# CAN_Humidity_Sensor_HB_LED_IR.net
KiCad netlist of a schematic drawn in Altium Designer
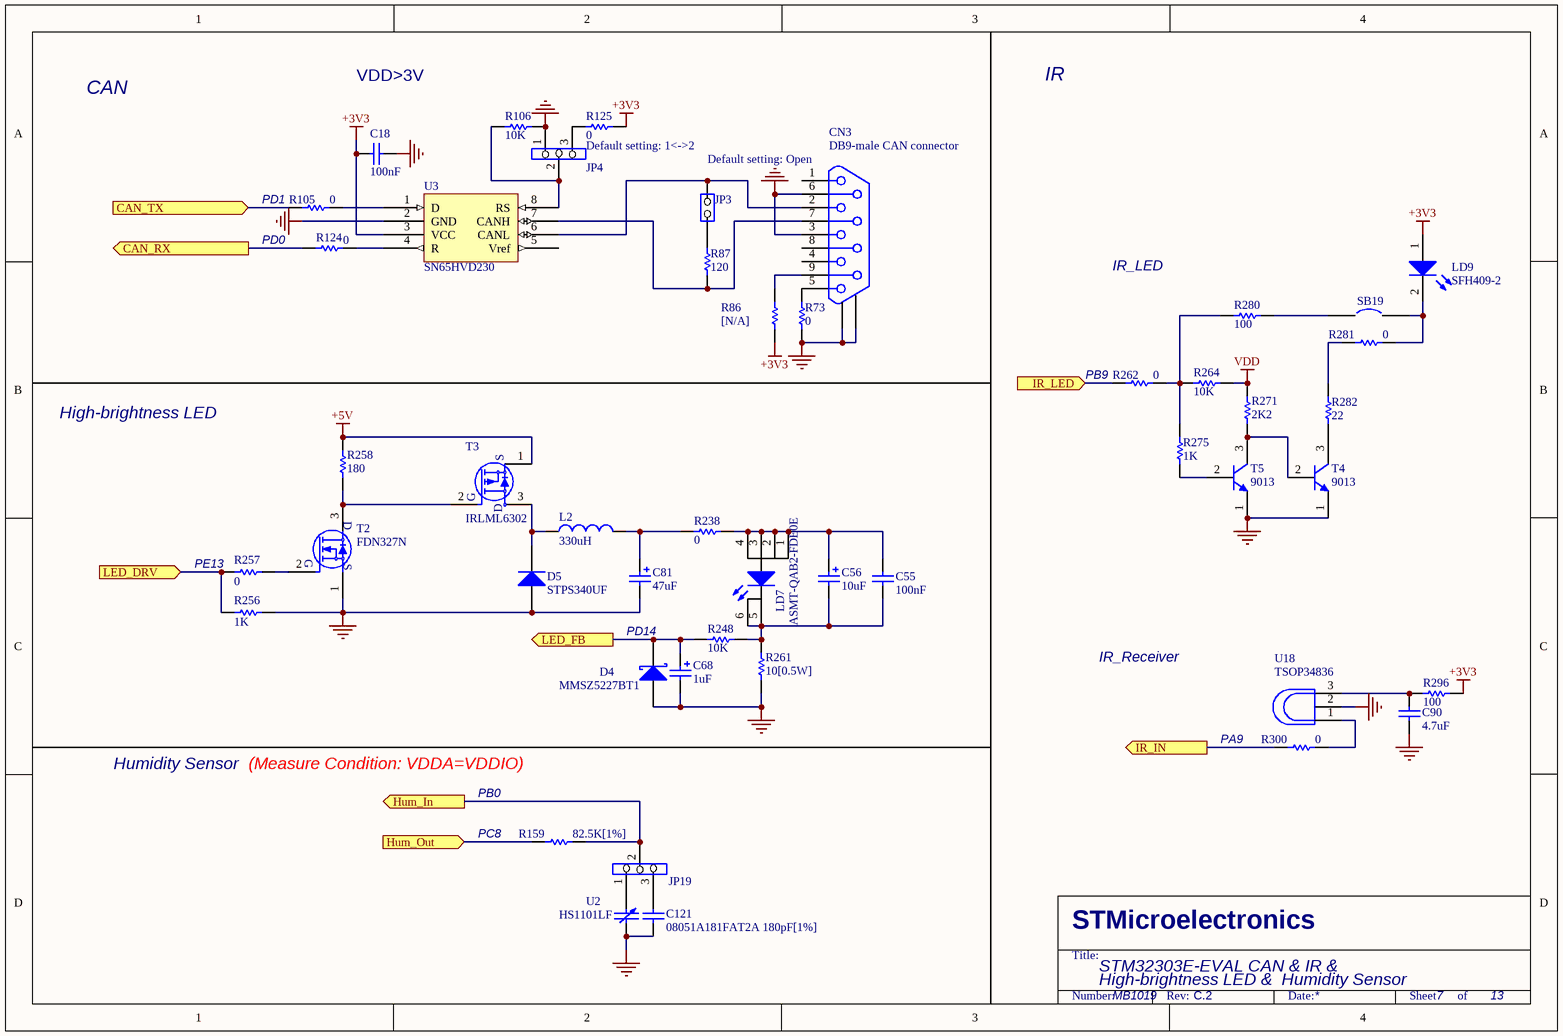
[diagram p0: CAN&Humidity_Sensor&HB_LED&IR.SchDoc]

(export (version "E")
  (design (tool "Eeschema 10.0.6"))
  (components
    (comp (ref "C18")
      (value "100nF")
      (footprint "0603C")
      (description "Capacitor")
      (fields (field (name "PUBLISHER") "Altium Limited"))
      (libsource (lib "Miscellaneous Devices") (part "CAP"))
    )
    (comp (ref "C55")
      (value "100nF")
      (footprint "0603C")
      (description "Capacitor")
      (fields (field (name "PUBLISHER") "Altium Limited"))
      (libsource (lib "Miscellaneous Devices") (part "Cap"))
    )
    (comp (ref "C56")
      (value "10uF")
      (footprint "TAN-A")
      (description "Polarized Capacitor (Radial)")
      (fields (field (name "PUBLISHER") "Altium Limited"))
      (libsource (lib "Miscellaneous Devices") (part "Cap Pol1"))
    )
    (comp (ref "C68")
      (value "1uF")
      (footprint "TAN-A")
      (description "Polarized Capacitor (Radial)")
      (fields (field (name "PUBLISHER") "Altium Limited"))
      (libsource (lib "Miscellaneous Devices") (part "Cap Pol1"))
    )
    (comp (ref "C81")
      (value "47uF")
      (footprint "C200M")
      (description "Polarized Capacitor (Radial)")
      (fields (field (name "PUBLISHER") "Altium Limited"))
      (libsource (lib "Miscellaneous Devices") (part "Cap Pol1"))
    )
    (comp (ref "C90")
      (value "4.7uF")
      (footprint "0603C")
      (description "Capacitor")
      (fields (field (name "PUBLISHER") "Altium Limited"))
      (libsource (lib "Miscellaneous Devices") (part "Cap"))
    )
    (comp (ref "C121")
      (value "08051A181FAT2A 180pF[1%]")
      (footprint "0805C")
      (description "Capacitor")
      (fields (field (name "PUBLISHER") "Altium Limited"))
      (libsource (lib "Miscellaneous Devices") (part "Cap"))
    )
    (comp (ref "CN3") (value "DB9-male CAN connector") (footprint "DB9/M") (libsource (lib "*") (part "DB9")))
    (comp (ref "D4")
      (value "MMSZ5227BT1")
      (footprint "SOD-123")
      (description "Schottky Diode")
      (fields (field (name "PUBLISHER") "Altium Limited"))
      (libsource (lib "Miscellaneous Devices") (part "D Schottky"))
    )
    (comp (ref "D5")
      (value "STPS340UF")
      (footprint "SMB")
      (description "Default Diode")
      (fields (field (name "PUBLISHER") "Altium Limited"))
      (libsource (lib "MB1019") (part "STPS340"))
    )
    (comp (ref "JP3") (value "~") (footprint "SIP2") (libsource (lib "*") (part "JP2")))
    (comp (ref "JP4") (value "~") (footprint "SIP3") (libsource (lib "") (part "Jumper3_1")))
    (comp (ref "JP19") (value "~") (footprint "SIP3") (libsource (lib "STR910_SCHLIB") (part "Jumper3")))
    (comp (ref "L2")
      (value "330uH")
      (footprint "SLF10145")
      (description "Inductor")
      (fields (field (name "PUBLISHER") "Altium Limited"))
      (libsource (lib "MB1019") (part "SLF10145T-331MR54-PF"))
    )
    (comp (ref "LD7")
      (value "ASMT-QAB2-FDE0E")
      (footprint "PLCC4")
      (description "High brightness LED")
      (fields (field (name "PUBLISHER") "Altium Limited"))
      (libsource (lib "MB1019") (part "HB_LED"))
    )
    (comp (ref "LD9")
      (value "SFH409-2")
      (footprint "D0.1L")
      (description "Typical RED, GREEN, YELLOW, AMBER GaAs LED")
      (fields (field (name "PUBLISHER") "Altium Limited"))
      (libsource (lib "Miscellaneous Devices") (part "LED2"))
    )
    (comp (ref "R73")
      (value "0")
      (footprint "0603R")
      (description "Resistor")
      (fields (field (name "PUBLISHER") "Altium Limited"))
      (libsource (lib "Miscellaneous Devices") (part "res1"))
    )
    (comp (ref "R86")
      (value "[N/A]")
      (footprint "0603R")
      (description "Resistor")
      (fields (field (name "PUBLISHER") "Altium Limited"))
      (libsource (lib "Miscellaneous Devices") (part "res1"))
    )
    (comp (ref "R87")
      (value "120")
      (footprint "0603R")
      (description "Resistor")
      (fields (field (name "PUBLISHER") "Altium Limited"))
      (libsource (lib "Miscellaneous Devices") (part "res1"))
    )
    (comp (ref "R105")
      (value "0")
      (footprint "0603R")
      (description "Resistor")
      (fields (field (name "PUBLISHER") "Altium Limited"))
      (libsource (lib "Miscellaneous Devices") (part "res1"))
    )
    (comp (ref "R106")
      (value "10K")
      (footprint "0603R")
      (description "Resistor")
      (fields (field (name "PUBLISHER") "Altium Limited"))
      (libsource (lib "Miscellaneous Devices") (part "res1"))
    )
    (comp (ref "R124")
      (value "0")
      (footprint "0603R")
      (description "Resistor")
      (fields (field (name "PUBLISHER") "Altium Limited"))
      (libsource (lib "Miscellaneous Devices") (part "Res1"))
    )
    (comp (ref "R125")
      (value "0")
      (footprint "0603R")
      (description "Resistor")
      (fields (field (name "PUBLISHER") "Altium Limited"))
      (libsource (lib "Miscellaneous Devices") (part "res1"))
    )
    (comp (ref "R159")
      (value "82.5K[1%]")
      (footprint "0603R")
      (description "Resistor")
      (fields (field (name "PUBLISHER") "Altium Limited"))
      (libsource (lib "Miscellaneous Devices") (part "Res1"))
    )
    (comp (ref "R238")
      (value "0")
      (footprint "0603R")
      (description "Resistor")
      (fields (field (name "PUBLISHER") "Altium Limited"))
      (libsource (lib "Miscellaneous Devices") (part "res1"))
    )
    (comp (ref "R248")
      (value "10K")
      (footprint "0603R")
      (description "Resistor")
      (fields (field (name "PUBLISHER") "Altium Limited"))
      (libsource (lib "Miscellaneous Devices") (part "res1"))
    )
    (comp (ref "R256")
      (value "1K")
      (footprint "0603R")
      (description "Resistor")
      (fields (field (name "PUBLISHER") "Altium Limited"))
      (libsource (lib "Miscellaneous Devices") (part "Res1"))
    )
    (comp (ref "R257")
      (value "0")
      (footprint "0603R")
      (description "Resistor")
      (fields (field (name "PUBLISHER") "Altium Limited"))
      (libsource (lib "Miscellaneous Devices") (part "Res1"))
    )
    (comp (ref "R258")
      (value "180")
      (footprint "0603R")
      (description "Resistor")
      (fields (field (name "PUBLISHER") "Altium Limited"))
      (libsource (lib "Miscellaneous Devices") (part "Res1"))
    )
    (comp (ref "R261")
      (value "10[0.5W]")
      (footprint "2010R")
      (description "Resistor")
      (fields (field (name "PUBLISHER") "Altium Limited"))
      (libsource (lib "Miscellaneous Devices") (part "Res1"))
    )
    (comp (ref "R262")
      (value "0")
      (footprint "0603R")
      (description "Resistor")
      (fields (field (name "PUBLISHER") "Altium Limited"))
      (libsource (lib "Miscellaneous Devices") (part "res1"))
    )
    (comp (ref "R264")
      (value "10K")
      (footprint "0603R")
      (description "Resistor")
      (fields (field (name "PUBLISHER") "Altium Limited"))
      (libsource (lib "Miscellaneous Devices") (part "Res1"))
    )
    (comp (ref "R271")
      (value "2K2")
      (footprint "0603R")
      (description "Resistor")
      (fields (field (name "PUBLISHER") "Altium Limited"))
      (libsource (lib "Miscellaneous Devices") (part "Res1"))
    )
    (comp (ref "R275")
      (value "1K")
      (footprint "0603R")
      (description "Resistor")
      (fields (field (name "PUBLISHER") "Altium Limited"))
      (libsource (lib "Miscellaneous Devices") (part "Res1"))
    )
    (comp (ref "R280")
      (value "100")
      (footprint "0603R")
      (description "Resistor")
      (fields (field (name "PUBLISHER") "Altium Limited"))
      (libsource (lib "Miscellaneous Devices") (part "Res1"))
    )
    (comp (ref "R281")
      (value "0")
      (footprint "0603R")
      (description "Resistor")
      (fields (field (name "PUBLISHER") "Altium Limited"))
      (libsource (lib "Miscellaneous Devices") (part "Res1"))
    )
    (comp (ref "R282")
      (value "22")
      (footprint "0603R")
      (description "Resistor")
      (fields (field (name "PUBLISHER") "Altium Limited"))
      (libsource (lib "Miscellaneous Devices") (part "Res1"))
    )
    (comp (ref "R296")
      (value "100")
      (footprint "0603R")
      (description "Resistor")
      (fields (field (name "PUBLISHER") "Altium Limited"))
      (libsource (lib "Miscellaneous Devices") (part "Res1"))
    )
    (comp (ref "R300")
      (value "0")
      (footprint "0603R")
      (description "Resistor")
      (fields (field (name "PUBLISHER") "Altium Limited"))
      (libsource (lib "Miscellaneous Devices") (part "Res1"))
    )
    (comp (ref "SB19")
      (value "~")
      (footprint "JP2_SMD")
      (description "Circuit Breaker")
      (fields (field (name "PUBLISHER") "Altium Limited"))
      (libsource (lib "Miscellaneous Devices") (part "Circuit Breaker"))
    )
    (comp (ref "T2") (value "FDN327N") (footprint "SOT-23") (libsource (lib "MB525") (part "2N7000")))
    (comp (ref "T3") (value "IRLML6302") (footprint "SOT-23") (libsource (lib "MB1019") (part "irlml6302")))
    (comp (ref "T4")
      (value "9013")
      (footprint "SOT-23")
      (description "NPN Bipolar Transistor")
      (fields (field (name "PUBLISHER") "Altium Limited"))
      (libsource (lib "Miscellaneous Devices") (part "NPN"))
    )
    (comp (ref "T5")
      (value "9013")
      (footprint "SOT-23")
      (description "NPN Bipolar Transistor")
      (fields (field (name "PUBLISHER") "Altium Limited"))
      (libsource (lib "Miscellaneous Devices") (part "NPN"))
    )
    (comp (ref "U2") (value "HS1101LF") (footprint "HS1101LF") (libsource (lib "MB1019") (part "HS1101LF")))
    (comp (ref "U3")
      (value "SN65HVD230")
      (footprint "SO8")
      (libsource (lib "STR910_SCHLIB") (part "SN65HVD230D"))
    )
    (comp (ref "U18") (value "TSOP34836") (footprint "TSOP348") (libsource (lib "MB901") (part "TSOP34838")))
  )
  (nets
    (net (code "1") (name "+3V3") (class "Default")
      (node (ref "C18") (pin "2") (pinfunction "2_2") (pintype "passive"))
      (node (ref "LD9") (pin "1") (pinfunction "A_1") (pintype "passive"))
      (node (ref "R125") (pin "2") (pinfunction "2_2") (pintype "passive"))
      (node (ref "R296") (pin "2") (pinfunction "2_2") (pintype "passive"))
      (node (ref "R86") (pin "1") (pinfunction "1_1") (pintype "passive"))
      (node (ref "U3") (pin "3") (pinfunction "VCC_3") (pintype "power_in"))
    )
    (net (code "2") (name "+5V") (class "Default")
      (node (ref "R258") (pin "1") (pinfunction "1_1") (pintype "passive"))
      (node (ref "T3") (pin "1") (pinfunction "S_1") (pintype "passive"))
    )
    (net (code "3") (name "/CAN_RX") (class "Default")
      (node (ref "R124") (pin "1") (pinfunction "1_1") (pintype "passive"))
    )
    (net (code "4") (name "/CAN_TX") (class "Default")
      (node (ref "R105") (pin "2") (pinfunction "2_2") (pintype "passive"))
    )
    (net (code "5") (name "/Hum_In") (class "Default")
      (node (ref "JP19") (pin "2") (pintype "passive"))
      (node (ref "R159") (pin "1") (pinfunction "1_1") (pintype "passive"))
    )
    (net (code "6") (name "/Hum_Out") (class "Default")
      (node (ref "R159") (pin "2") (pinfunction "2_2") (pintype "passive"))
    )
    (net (code "7") (name "/IR_IN") (class "Default")
      (node (ref "R300") (pin "1") (pinfunction "1_1") (pintype "passive"))
    )
    (net (code "8") (name "/IR_LED") (class "Default")
      (node (ref "R262") (pin "2") (pinfunction "2_2") (pintype "passive"))
    )
    (net (code "9") (name "/LED_DRV") (class "Default")
      (node (ref "R256") (pin "2") (pinfunction "2_2") (pintype "passive"))
      (node (ref "R257") (pin "1") (pinfunction "1_1") (pintype "passive"))
    )
    (net (code "10") (name "/LED_FB") (class "Default")
      (node (ref "C68") (pin "1") (pinfunction "1_1") (pintype "passive"))
      (node (ref "D4") (pin "2") (pinfunction "K_2") (pintype "passive"))
      (node (ref "R248") (pin "1") (pinfunction "1_1") (pintype "passive"))
    )
    (net (code "11") (name "GND") (class "Default")
      (node (ref "C121") (pin "1") (pinfunction "1_1") (pintype "passive"))
      (node (ref "C18") (pin "1") (pinfunction "1_1") (pintype "passive"))
      (node (ref "C68") (pin "2") (pinfunction "2_2") (pintype "passive"))
      (node (ref "C81") (pin "2") (pinfunction "2_2") (pintype "passive"))
      (node (ref "C90") (pin "2") (pinfunction "2_2") (pintype "passive"))
      (node (ref "CN3") (pin "0") (pinfunction "10_0") (pintype "passive"))
      (node (ref "CN3") (pin "3") (pinfunction "3_3") (pintype "passive"))
      (node (ref "CN3") (pin "6") (pinfunction "6_6") (pintype "passive"))
      (node (ref "D4") (pin "1") (pinfunction "A_1") (pintype "passive"))
      (node (ref "D5") (pin "1") (pinfunction "A_1") (pintype "passive"))
      (node (ref "JP4") (pin "1") (pintype "passive"))
      (node (ref "R106") (pin "2") (pinfunction "2_2") (pintype "passive"))
      (node (ref "R256") (pin "1") (pinfunction "1_1") (pintype "passive"))
      (node (ref "R261") (pin "1") (pinfunction "1_1") (pintype "passive"))
      (node (ref "R73") (pin "1") (pinfunction "1_1") (pintype "passive"))
      (node (ref "T2") (pin "1") (pinfunction "S_1") (pintype "passive"))
      (node (ref "T4") (pin "1") (pinfunction "E_1") (pintype "passive"))
      (node (ref "T5") (pin "1") (pinfunction "E_1") (pintype "passive"))
      (node (ref "U18") (pin "2") (pinfunction "GND_2") (pintype "passive"))
      (node (ref "U2") (pin "2") (pinfunction "2_2") (pintype "passive"))
      (node (ref "U3") (pin "2") (pinfunction "GND_2") (pintype "power_in"))
    )
    (net (code "12") (name "Net-(C55-Pad1)") (class "Default")
      (node (ref "C55") (pin "1") (pinfunction "1_1") (pintype "passive"))
      (node (ref "C56") (pin "2") (pinfunction "2_2") (pintype "passive"))
      (node (ref "LD7") (pin "5") (pinfunction "K_5") (pintype "passive"))
      (node (ref "LD7") (pin "6") (pinfunction "K_6") (pintype "passive"))
      (node (ref "R248") (pin "2") (pinfunction "2_2") (pintype "passive"))
      (node (ref "R261") (pin "2") (pinfunction "2_2") (pintype "passive"))
    )
    (net (code "13") (name "Net-(C55-Pad2)") (class "Default")
      (node (ref "C55") (pin "2") (pinfunction "2_2") (pintype "passive"))
      (node (ref "C56") (pin "1") (pinfunction "1_1") (pintype "passive"))
      (node (ref "LD7") (pin "1") (pinfunction "A_1") (pintype "passive"))
      (node (ref "LD7") (pin "2") (pinfunction "A_2") (pintype "passive"))
      (node (ref "LD7") (pin "3") (pinfunction "A_3") (pintype "passive"))
      (node (ref "LD7") (pin "4") (pinfunction "A_4") (pintype "passive"))
      (node (ref "R238") (pin "2") (pinfunction "2_2") (pintype "passive"))
    )
    (net (code "14") (name "Net-(C81-Pad1)") (class "Default")
      (node (ref "C81") (pin "1") (pinfunction "1_1") (pintype "passive"))
      (node (ref "L2") (pin "2") (pinfunction "2_2") (pintype "passive"))
      (node (ref "R238") (pin "1") (pinfunction "1_1") (pintype "passive"))
    )
    (net (code "15") (name "Net-(C121-Pad2)") (class "Default")
      (node (ref "C121") (pin "2") (pinfunction "2_2") (pintype "passive"))
      (node (ref "JP19") (pin "3") (pintype "passive"))
    )
    (net (code "16") (name "Net-(CN3-Pad5)") (class "Default")
      (node (ref "CN3") (pin "5") (pinfunction "5_5") (pintype "passive"))
      (node (ref "R73") (pin "2") (pinfunction "2_2") (pintype "passive"))
    )
    (net (code "17") (name "Net-(CN3-Pad9)") (class "Default")
      (node (ref "CN3") (pin "9") (pinfunction "9_9") (pintype "passive"))
      (node (ref "R86") (pin "2") (pinfunction "2_2") (pintype "passive"))
    )
    (net (code "18") (name "Net-(D5-K)") (class "Default")
      (node (ref "D5") (pin "2") (pinfunction "K_2") (pintype "passive"))
      (node (ref "L2") (pin "1") (pinfunction "1_1") (pintype "passive"))
      (node (ref "T3") (pin "3") (pinfunction "D_3") (pintype "passive"))
    )
    (net (code "19") (name "Net-(JP3-COMMON)") (class "Default")
      (node (ref "JP3") (pin "1") (pinfunction "COMMON_1") (pintype "passive"))
      (node (ref "R87") (pin "2") (pinfunction "2_2") (pintype "passive"))
    )
    (net (code "20") (name "Net-(JP3-NO)") (class "Default")
      (node (ref "CN3") (pin "2") (pinfunction "2_2") (pintype "passive"))
      (node (ref "JP3") (pin "2") (pinfunction "NO_2") (pintype "passive"))
      (node (ref "U3") (pin "6") (pinfunction "CANL_6") (pintype "bidirectional"))
    )
    (net (code "21") (name "Net-(JP4-Pad3)") (class "Default")
      (node (ref "JP4") (pin "3") (pintype "passive"))
      (node (ref "R125") (pin "1") (pinfunction "1_1") (pintype "passive"))
    )
    (net (code "22") (name "Net-(JP19-Pad1)") (class "Default")
      (node (ref "JP19") (pin "1") (pintype "passive"))
      (node (ref "U2") (pin "1") (pinfunction "1_1") (pintype "passive"))
    )
    (net (code "23") (name "Net-(LD9-K)") (class "Default")
      (node (ref "LD9") (pin "2") (pinfunction "K_2") (pintype "passive"))
      (node (ref "R281") (pin "2") (pinfunction "2_2") (pintype "passive"))
      (node (ref "SB19") (pin "2") (pinfunction "2_2") (pintype "passive"))
    )
    (net (code "24") (name "Net-(R262-Pad1)") (class "Default")
      (node (ref "R262") (pin "1") (pinfunction "1_1") (pintype "passive"))
      (node (ref "R264") (pin "2") (pinfunction "2_2") (pintype "passive"))
      (node (ref "R275") (pin "1") (pinfunction "1_1") (pintype "passive"))
      (node (ref "R280") (pin "2") (pinfunction "2_2") (pintype "passive"))
    )
    (net (code "25") (name "Net-(R280-Pad1)") (class "Default")
      (node (ref "R280") (pin "1") (pinfunction "1_1") (pintype "passive"))
      (node (ref "SB19") (pin "1") (pinfunction "1_1") (pintype "passive"))
    )
    (net (code "26") (name "Net-(R281-Pad1)") (class "Default")
      (node (ref "R281") (pin "1") (pinfunction "1_1") (pintype "passive"))
      (node (ref "R282") (pin "2") (pinfunction "2_2") (pintype "passive"))
    )
    (net (code "27") (name "Net-(T2-D)") (class "Default")
      (node (ref "R258") (pin "2") (pinfunction "2_2") (pintype "passive"))
      (node (ref "T2") (pin "3") (pinfunction "D_3") (pintype "passive"))
      (node (ref "T3") (pin "2") (pinfunction "G_2") (pintype "passive"))
    )
    (net (code "28") (name "Net-(T2-G)") (class "Default")
      (node (ref "R257") (pin "2") (pinfunction "2_2") (pintype "passive"))
      (node (ref "T2") (pin "2") (pinfunction "G_2") (pintype "passive"))
    )
    (net (code "29") (name "Net-(T4-B)") (class "Default")
      (node (ref "R271") (pin "1") (pinfunction "1_1") (pintype "passive"))
      (node (ref "T4") (pin "2") (pinfunction "B_2") (pintype "passive"))
      (node (ref "T5") (pin "3") (pinfunction "C_3") (pintype "passive"))
    )
    (net (code "30") (name "Net-(T4-C)") (class "Default")
      (node (ref "R282") (pin "1") (pinfunction "1_1") (pintype "passive"))
      (node (ref "T4") (pin "3") (pinfunction "C_3") (pintype "passive"))
    )
    (net (code "31") (name "Net-(T5-B)") (class "Default")
      (node (ref "R275") (pin "2") (pinfunction "2_2") (pintype "passive"))
      (node (ref "T5") (pin "2") (pinfunction "B_2") (pintype "passive"))
    )
    (net (code "32") (name "Net-(U3-CANH)") (class "Default")
      (node (ref "CN3") (pin "7") (pinfunction "7_7") (pintype "passive"))
      (node (ref "R87") (pin "1") (pinfunction "1_1") (pintype "passive"))
      (node (ref "U3") (pin "7") (pinfunction "CANH_7") (pintype "bidirectional"))
    )
    (net (code "33") (name "Net-(U3-D)") (class "Default")
      (node (ref "R105") (pin "1") (pinfunction "1_1") (pintype "passive"))
      (node (ref "U3") (pin "1") (pinfunction "D_1") (pintype "input"))
    )
    (net (code "34") (name "Net-(U3-R)") (class "Default")
      (node (ref "R124") (pin "2") (pinfunction "2_2") (pintype "passive"))
      (node (ref "U3") (pin "4") (pinfunction "R_4") (pintype "output"))
    )
    (net (code "35") (name "Net-(U3-RS)") (class "Default")
      (node (ref "JP4") (pin "2") (pintype "passive"))
      (node (ref "R106") (pin "1") (pinfunction "1_1") (pintype "passive"))
      (node (ref "U3") (pin "8") (pinfunction "RS_8") (pintype "input"))
    )
    (net (code "36") (name "Net-(U18-OUT)") (class "Default")
      (node (ref "R300") (pin "2") (pinfunction "2_2") (pintype "passive"))
      (node (ref "U18") (pin "1") (pinfunction "OUT_1") (pintype "passive"))
    )
    (net (code "37") (name "Net-(U18-Vs)") (class "Default")
      (node (ref "C90") (pin "1") (pinfunction "1_1") (pintype "passive"))
      (node (ref "R296") (pin "1") (pinfunction "1_1") (pintype "passive"))
      (node (ref "U18") (pin "3") (pinfunction "Vs_3") (pintype "passive"))
    )
    (net (code "38") (name "VDD") (class "Default")
      (node (ref "R264") (pin "1") (pinfunction "1_1") (pintype "passive"))
      (node (ref "R271") (pin "2") (pinfunction "2_2") (pintype "passive"))
    )
    (net (code "39") (name "unconnected-(CN3-Pad1)") (class "Default")
      (node (ref "CN3") (pin "1") (pinfunction "1_1") (pintype "passive"))
    )
    (net (code "40") (name "unconnected-(CN3-Pad4)") (class "Default")
      (node (ref "CN3") (pin "4") (pinfunction "4_4") (pintype "passive"))
    )
    (net (code "41") (name "unconnected-(CN3-Pad8)") (class "Default")
      (node (ref "CN3") (pin "8") (pinfunction "8_8") (pintype "passive"))
    )
    (net (code "42") (name "unconnected-(U3-Vref-Pad5)") (class "Default")
      (node (ref "U3") (pin "5") (pinfunction "Vref_5") (pintype "output"))
    )
  )
)
